# Accelerometer.net
KiCad netlist of a schematic drawn in Altium Designer
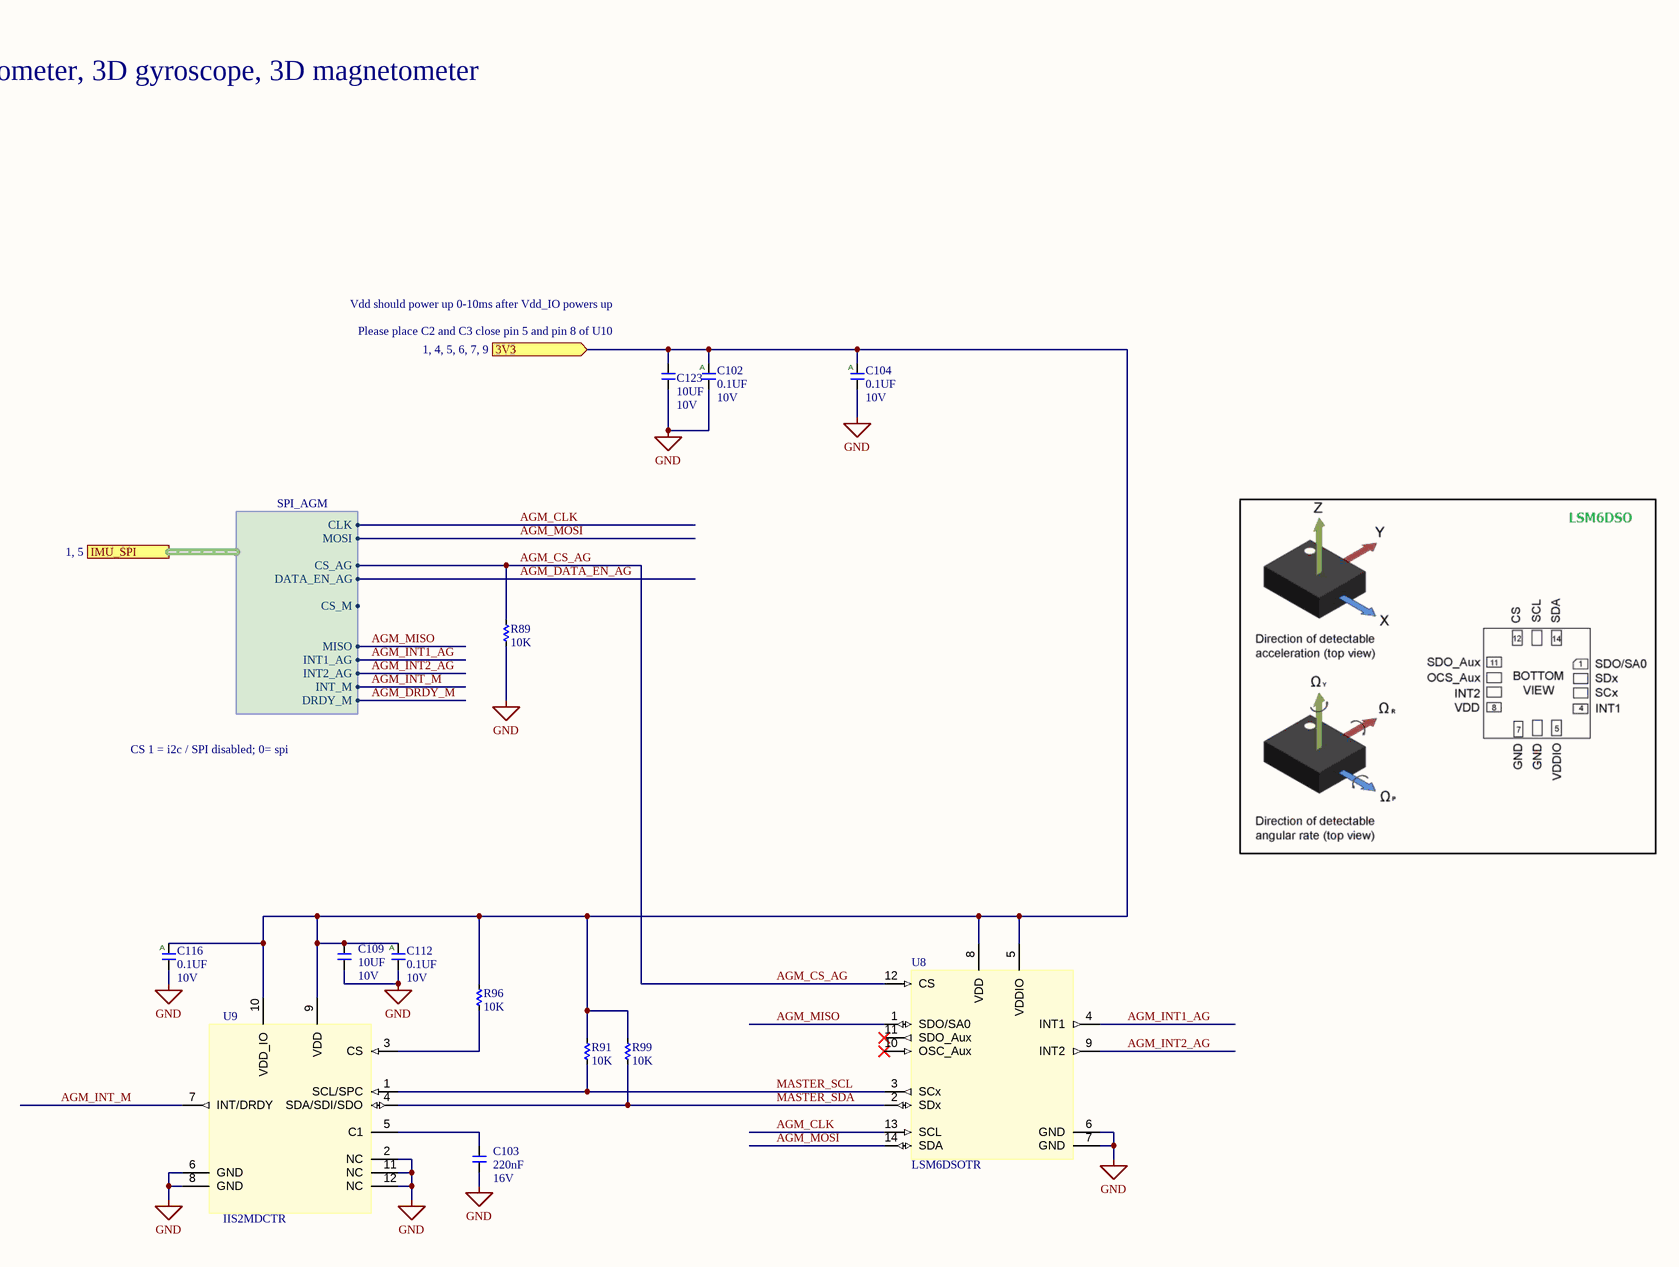
[diagram p0: Accelerometer.SchDoc]

(export (version "E")
  (design (tool "Eeschema 10.0.6"))
  (components
    (comp (ref "C102")
      (value "0.1UF")
      (footprint "C0201")
      (description "CAP, CER, X6S, 0.1uF, 10V, 10%, 0201, AUTOGRADE")
      (fields
        (field (name "MFG") "MURATA")
        (field (name "VOLTAGE") "10V")
        (field (name "Comment") "__Template_Cap_Auto")
      )
      (libsource (lib "AltiumReleaseLibDB") (part "__Template_Cap_Auto"))
    )
    (comp (ref "C103")
      (value "220nF")
      (footprint "C0402")
      (description "CAP CER 0402 220NF 16VDC X7R")
      (fields
        (field (name "MFG") "KEMET")
        (field (name "VOLTAGE") "16V")
        (field (name "Comment") "__Template_Cap")
      )
      (libsource (lib "AltiumReleaseLibDB") (part "__Template_Cap"))
    )
    (comp (ref "C104")
      (value "0.1UF")
      (footprint "C0201")
      (description "CAP, CER, X6S, 0.1uF, 10V, 10%, 0201, AUTOGRADE")
      (fields
        (field (name "MFG") "MURATA")
        (field (name "VOLTAGE") "10V")
        (field (name "Comment") "__Template_Cap_Auto")
      )
      (libsource (lib "AltiumReleaseLibDB") (part "__Template_Cap_Auto"))
    )
    (comp (ref "C109")
      (value "10UF")
      (footprint "C0402")
      (description "CAP, CER, X5R, 10uF, 10V, 20%, 0402, 0.7mm T")
      (fields
        (field (name "MFG") "SAMSUNG")
        (field (name "VOLTAGE") "10V")
        (field (name "Comment") "__Template_Cap")
      )
      (libsource (lib "AltiumReleaseLibDB") (part "__Template_Cap"))
    )
    (comp (ref "C112")
      (value "0.1UF")
      (footprint "C0201")
      (description "CAP, CER, X6S, 0.1uF, 10V, 10%, 0201, AUTOGRADE")
      (fields
        (field (name "MFG") "MURATA")
        (field (name "VOLTAGE") "10V")
        (field (name "Comment") "__Template_Cap_Auto")
      )
      (libsource (lib "AltiumReleaseLibDB") (part "__Template_Cap_Auto"))
    )
    (comp (ref "C116")
      (value "0.1UF")
      (footprint "C0201")
      (description "CAP, CER, X6S, 0.1uF, 10V, 10%, 0201, AUTOGRADE")
      (fields
        (field (name "MFG") "MURATA")
        (field (name "VOLTAGE") "10V")
        (field (name "Comment") "__Template_Cap_Auto")
      )
      (libsource (lib "AltiumReleaseLibDB") (part "__Template_Cap_Auto"))
    )
    (comp (ref "C123")
      (value "10UF")
      (footprint "C0402")
      (description "CAP, CER, X5R, 10uF, 10V, 20%, 0402, 0.7mm T")
      (fields
        (field (name "MFG") "SAMSUNG")
        (field (name "VOLTAGE") "10V")
        (field (name "Comment") "__Template_Cap")
      )
      (libsource (lib "AltiumReleaseLibDB") (part "__Template_Cap"))
    )
    (comp (ref "R89")
      (value "10K")
      (footprint "R0201")
      (description "RES, 10K, 1%, 1/20W, 0201, AUTOGRADE")
      (fields (field (name "MFG") "PANASONIC") (field (name "Comment") "__Template_Resistor"))
      (libsource (lib "AltiumReleaseLibDB") (part "__Template_Resistor"))
    )
    (comp (ref "R91")
      (value "10K")
      (footprint "R0201")
      (description "RES, 10K, 1%, 1/20W, 0201, AUTOGRADE")
      (fields (field (name "MFG") "PANASONIC") (field (name "Comment") "__Template_Resistor"))
      (libsource (lib "AltiumReleaseLibDB") (part "__Template_Resistor"))
    )
    (comp (ref "R96")
      (value "10K")
      (footprint "R0201")
      (description "RES, 10K, 1%, 1/20W, 0201, AUTOGRADE")
      (fields (field (name "MFG") "PANASONIC") (field (name "Comment") "__Template_Resistor"))
      (libsource (lib "AltiumReleaseLibDB") (part "__Template_Resistor"))
    )
    (comp (ref "R99")
      (value "10K")
      (footprint "R0201")
      (description "RES, 10K, 1%, 1/20W, 0201, AUTOGRADE")
      (fields (field (name "MFG") "PANASONIC") (field (name "Comment") "__Template_Resistor"))
      (libsource (lib "AltiumReleaseLibDB") (part "__Template_Resistor"))
    )
    (comp (ref "U8")
      (value "SENSOR_ST_LSM6DSOTR")
      (footprint "14-LGA")
      (description "Accelerometer, Gyroscope, 6 Axis Sensor I²C, SPI Output")
      (fields (field (name "MFG") "STMicroelectronics") (field (name "MFG P/N") "LSM6DSOTR"))
      (libsource (lib "Cortes_Gebru_v05_Rev03") (part "LSM6DSOTR"))
    )
    (comp (ref "U9")
      (value "SENSOR_ST_IIS2MDCTR")
      (footprint "12-LGA")
      (description "SENSOR MR I2C/SPI 12LGA")
      (fields (field (name "MFG") "STMicroelectronics") (field (name "MFG P/N") "IIS2MDCTR"))
      (libsource (lib "Cortes_Gebru_v05_Rev03") (part "IIS2MDCTR"))
    )
  )
  (nets
    (net (code "2") (name "/3V3") (class "Default")
      (node (ref "C102") (pin "1") (pintype "passive"))
      (node (ref "C104") (pin "1") (pintype "passive"))
      (node (ref "C109") (pin "1") (pintype "passive"))
      (node (ref "C112") (pin "1") (pintype "passive"))
      (node (ref "C116") (pin "1") (pintype "passive"))
      (node (ref "C123") (pin "1") (pintype "passive"))
      (node (ref "R91") (pin "2") (pintype "passive"))
      (node (ref "R96") (pin "2") (pintype "passive"))
      (node (ref "R99") (pin "2") (pintype "passive"))
      (node (ref "U8") (pin "5") (pinfunction "VDDIO_5") (pintype "power_in"))
      (node (ref "U8") (pin "8") (pinfunction "VDD_8") (pintype "power_in"))
      (node (ref "U9") (pin "10") (pinfunction "VDD_IO_10") (pintype "power_in"))
      (node (ref "U9") (pin "9") (pinfunction "VDD_9") (pintype "power_in"))
    )
    (net (code "3") (name "/AGM_CLK") (class "Default")
      (node (ref "U8") (pin "13") (pinfunction "SCL_13") (pintype "input"))
    )
    (net (code "4") (name "/AGM_CS_AG") (class "Default")
      (node (ref "R89") (pin "2") (pintype "passive"))
      (node (ref "U8") (pin "12") (pinfunction "CS_12") (pintype "input"))
    )
    (net (code "7") (name "/AGM_INT1_AG") (class "Default")
      (node (ref "U8") (pin "4") (pinfunction "INT1_4") (pintype "output"))
    )
    (net (code "8") (name "/AGM_INT2_AG") (class "Default")
      (node (ref "U8") (pin "9") (pinfunction "INT2_9") (pintype "output"))
    )
    (net (code "9") (name "/AGM_INT_M") (class "Default")
      (node (ref "U9") (pin "7") (pinfunction "INT/DRDY_7") (pintype "output"))
    )
    (net (code "10") (name "/AGM_MISO") (class "Default")
      (node (ref "U8") (pin "1") (pinfunction "SDO/SA0_1") (pintype "bidirectional"))
    )
    (net (code "11") (name "/AGM_MOSI") (class "Default")
      (node (ref "U8") (pin "14") (pinfunction "SDA_14") (pintype "bidirectional"))
    )
    (net (code "12") (name "/MASTER_SCL") (class "Default")
      (node (ref "R91") (pin "1") (pintype "passive"))
      (node (ref "U8") (pin "3") (pinfunction "SCx_3") (pintype "output"))
      (node (ref "U9") (pin "1") (pinfunction "SCL/SPC_1") (pintype "input"))
    )
    (net (code "13") (name "/MASTER_SDA") (class "Default")
      (node (ref "R99") (pin "1") (pintype "passive"))
      (node (ref "U8") (pin "2") (pinfunction "SDx_2") (pintype "bidirectional"))
      (node (ref "U9") (pin "4") (pinfunction "SDA/SDI/SDO_4") (pintype "bidirectional"))
    )
    (net (code "15") (name "GND") (class "Default")
      (node (ref "C102") (pin "2") (pintype "passive"))
      (node (ref "C103") (pin "2") (pintype "passive"))
      (node (ref "C104") (pin "2") (pintype "passive"))
      (node (ref "C109") (pin "2") (pintype "passive"))
      (node (ref "C112") (pin "2") (pintype "passive"))
      (node (ref "C116") (pin "2") (pintype "passive"))
      (node (ref "C123") (pin "2") (pintype "passive"))
      (node (ref "R89") (pin "1") (pintype "passive"))
      (node (ref "U8") (pin "6") (pinfunction "GND_6") (pintype "power_in"))
      (node (ref "U8") (pin "7") (pinfunction "GND_7") (pintype "power_in"))
      (node (ref "U9") (pin "11") (pinfunction "NC_11") (pintype "passive"))
      (node (ref "U9") (pin "12") (pinfunction "NC_12") (pintype "passive"))
      (node (ref "U9") (pin "2") (pinfunction "NC_2") (pintype "passive"))
      (node (ref "U9") (pin "6") (pinfunction "GND_6") (pintype "power_in"))
      (node (ref "U9") (pin "8") (pinfunction "GND_8") (pintype "power_in"))
    )
    (net (code "16") (name "Net-(U9-C1)") (class "Default")
      (node (ref "C103") (pin "1") (pintype "passive"))
      (node (ref "U9") (pin "5") (pinfunction "C1_5") (pintype "passive"))
    )
    (net (code "17") (name "Net-(U9-CS)") (class "Default")
      (node (ref "R96") (pin "1") (pintype "passive"))
      (node (ref "U9") (pin "3") (pinfunction "CS_3") (pintype "input"))
    )
    (net (code "18") (name "unconnected-(U8-OSC_Aux-Pad10)") (class "Default")
      (node (ref "U8") (pin "10") (pinfunction "OSC_Aux_10") (pintype "input+no_connect"))
    )
    (net (code "19") (name "unconnected-(U8-SDO_Aux-Pad11)") (class "Default")
      (node (ref "U8") (pin "11") (pinfunction "SDO_Aux_11") (pintype "output+no_connect"))
    )
  )
)
